# G431_Dev_V2.net
KiCad netlist of a schematic drawn in Altium Designer
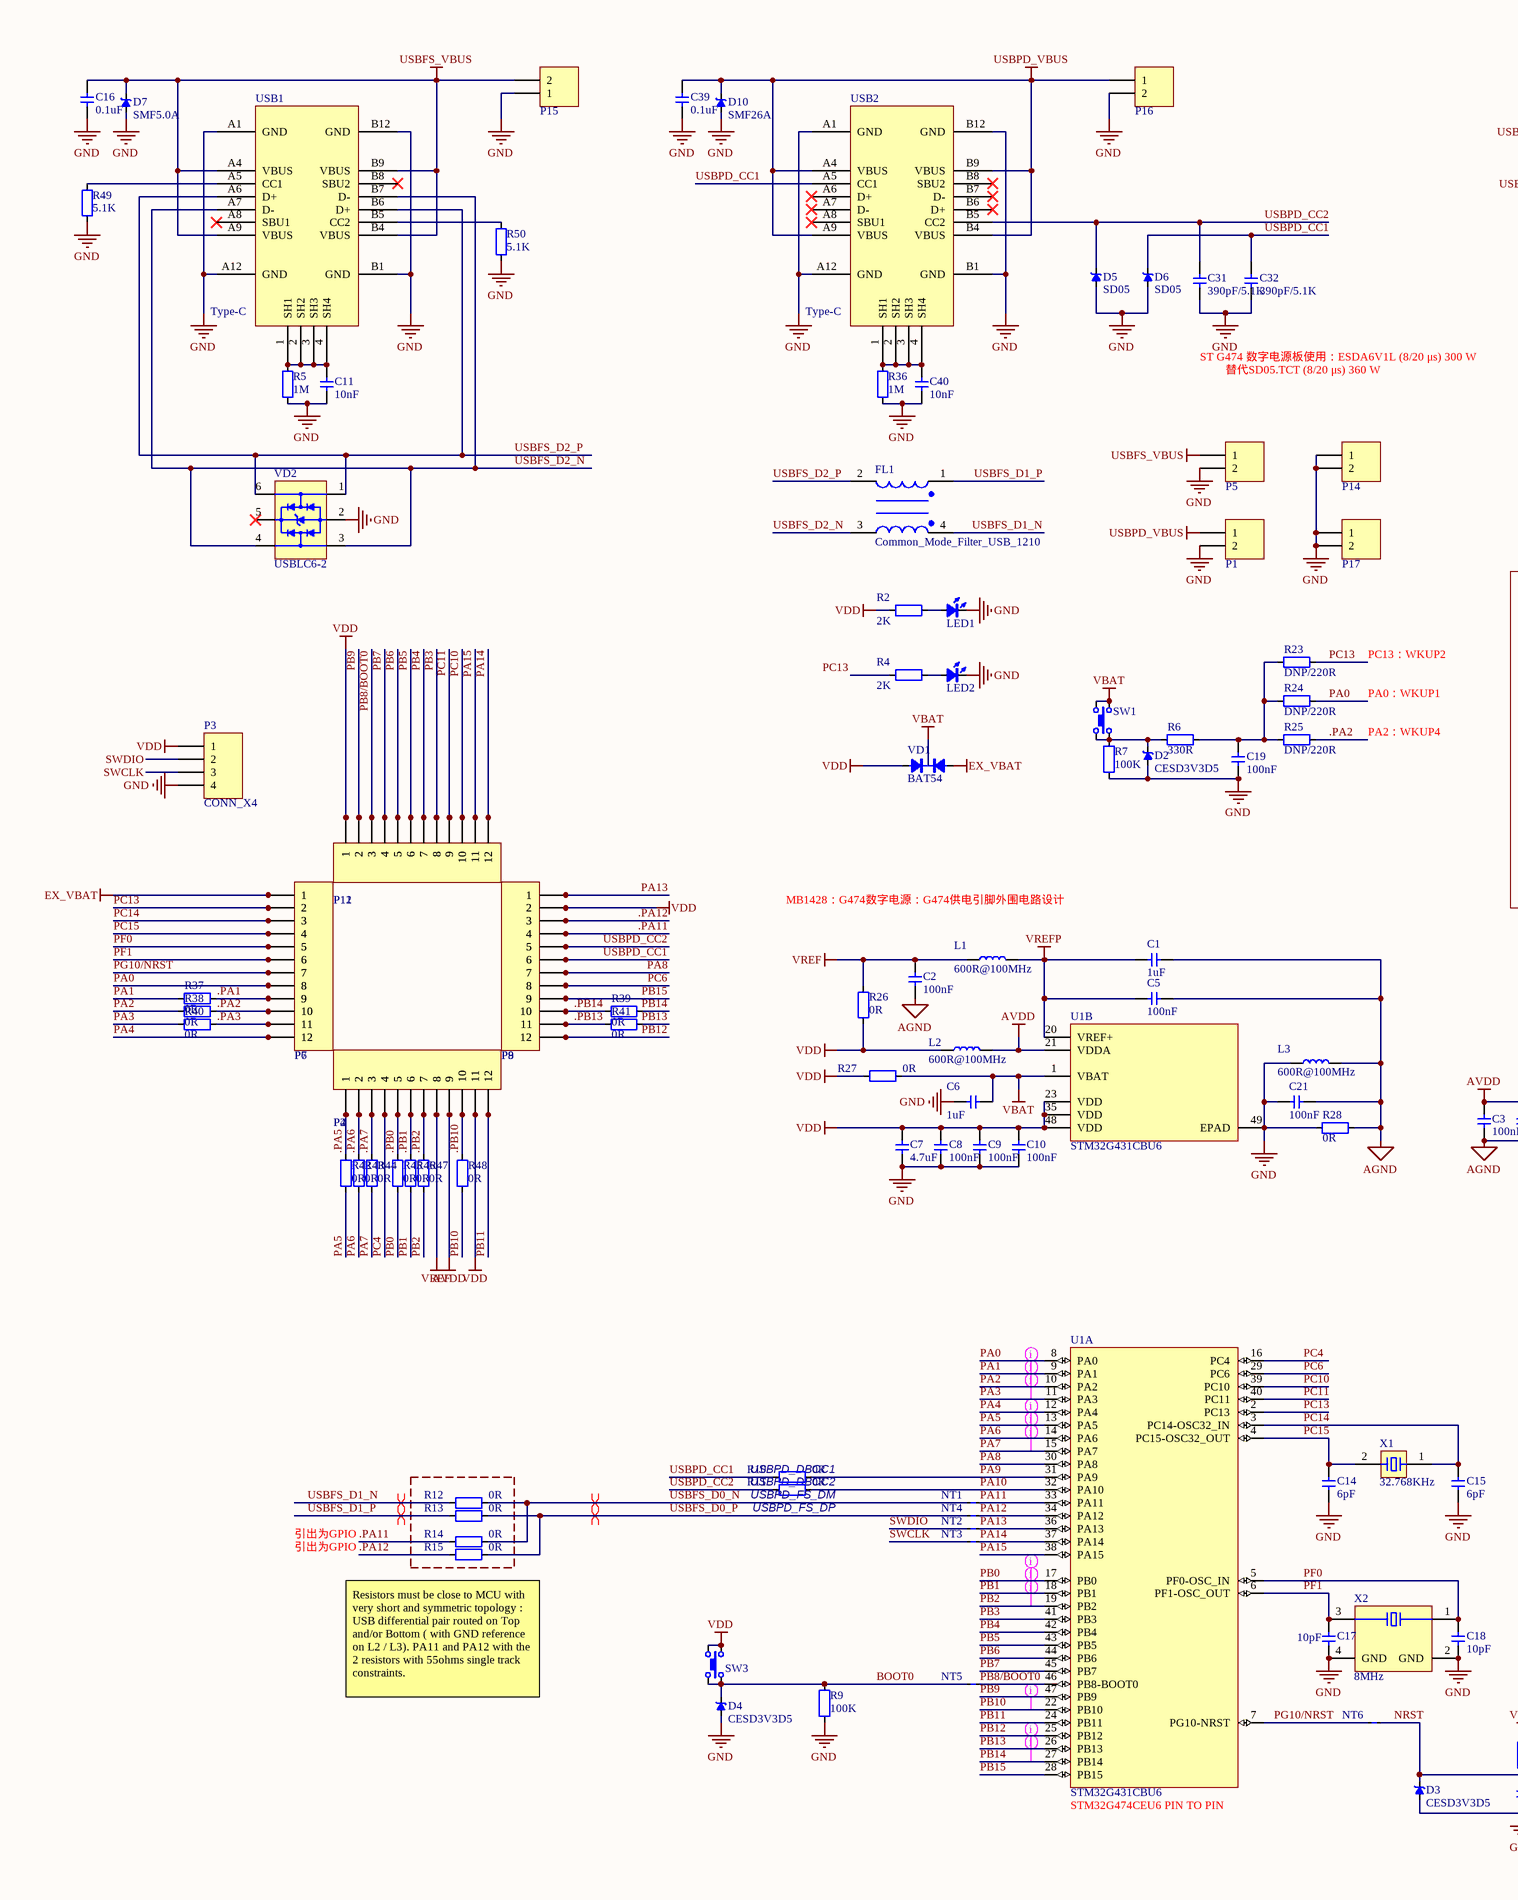
[diagram p0: G431_Dev_V2.SchDoc, left]
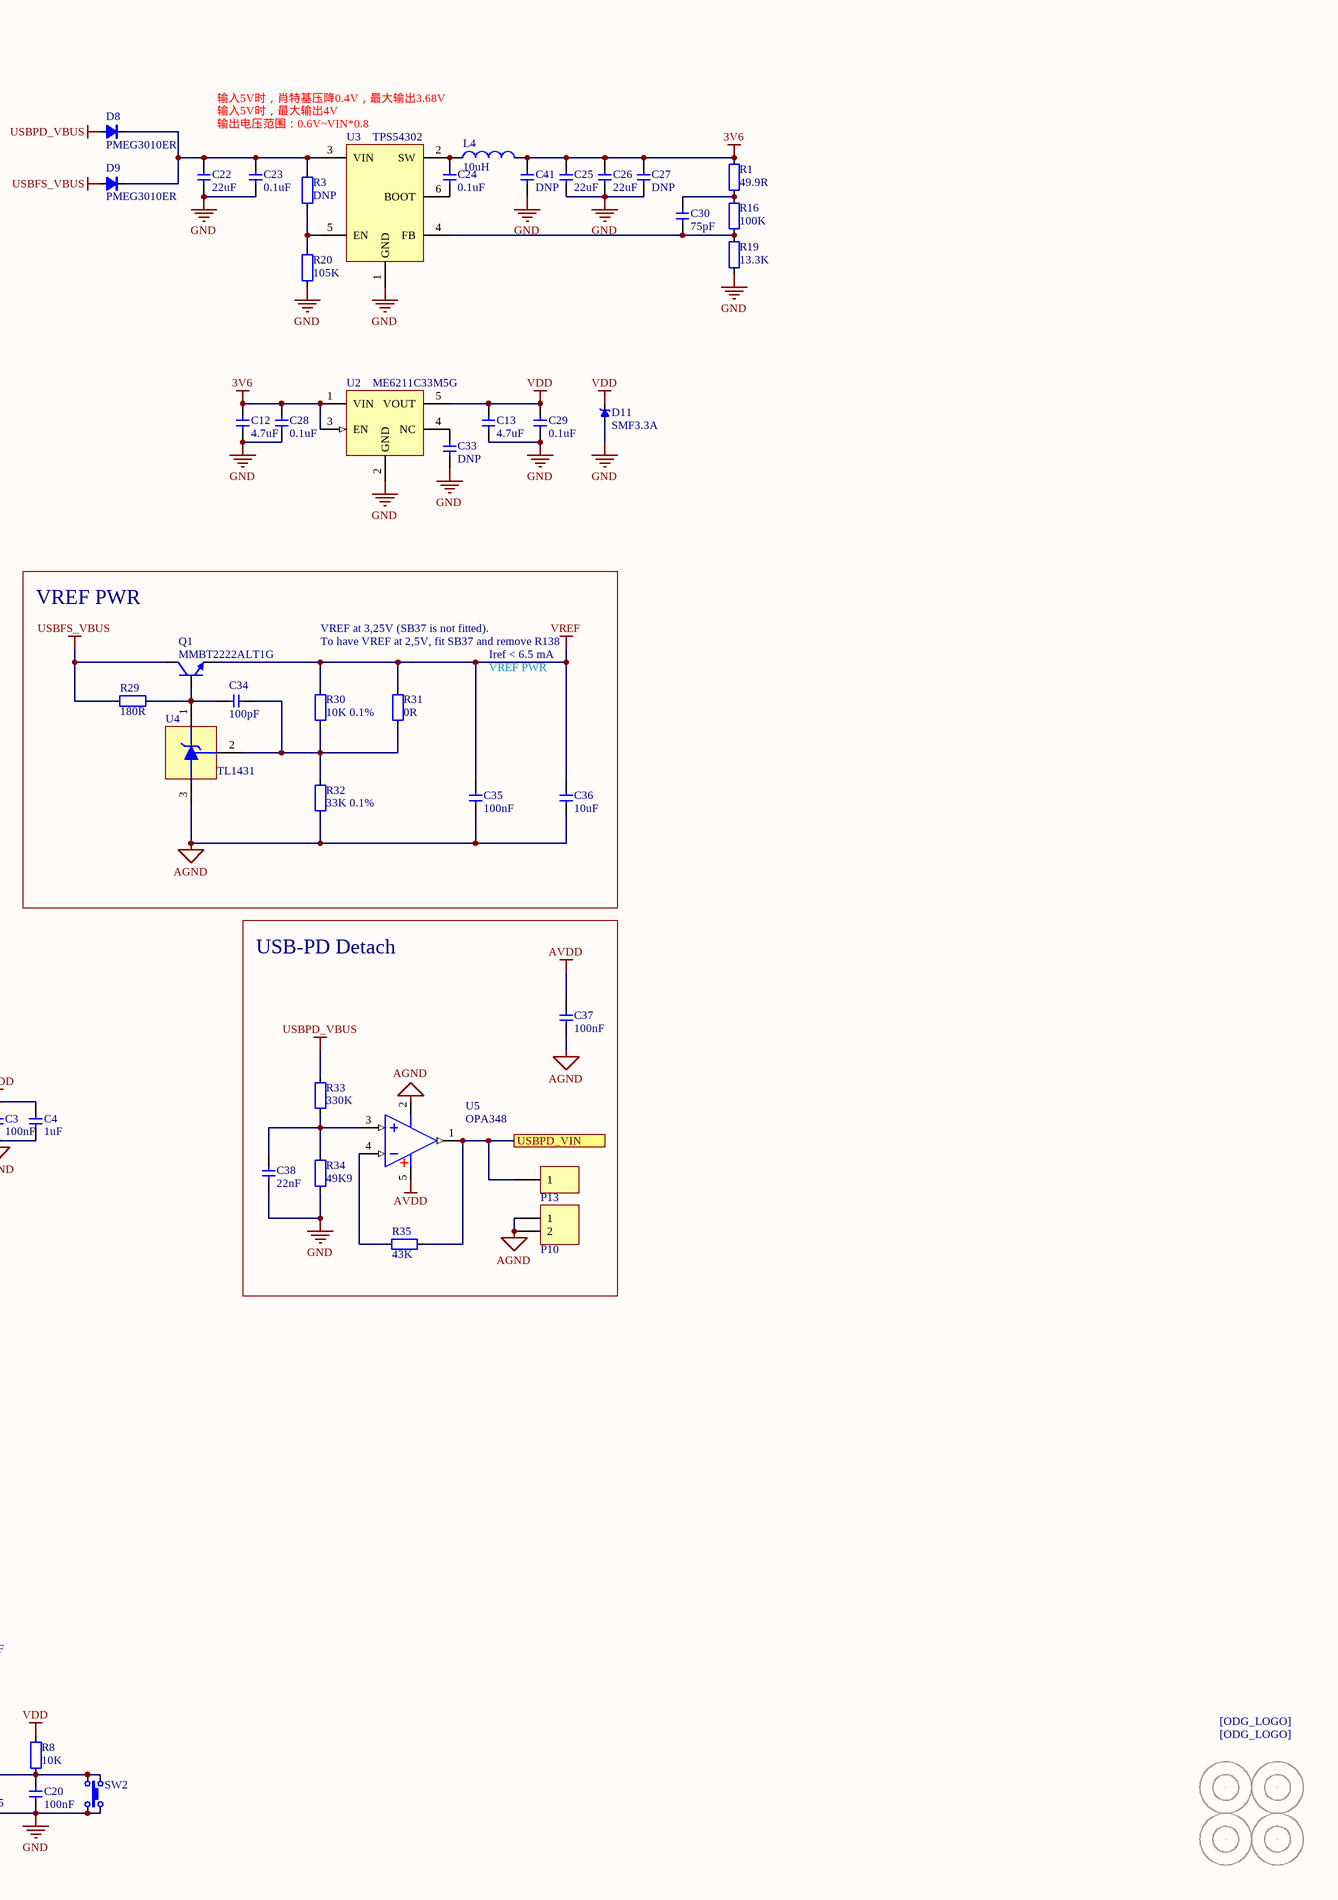
[diagram p1: G431_Dev_V2.SchDoc, right]

(export (version "E")
  (design (tool "Eeschema 10.0.6"))
  (components
    (comp (ref "*1")
      (value "ODG_LOGO")
      (footprint "ODG_LOGO")
      (libsource (lib "ODG_AD_Lib") (part "ODG_LOGO"))
    )
    (comp (ref "*2")
      (value "ODG_LOGO")
      (footprint "ODG_LOGO")
      (libsource (lib "ODG_AD_Lib") (part "ODG_LOGO"))
    )
    (comp (ref "C1")
      (value "1uF")
      (footprint "C0603")
      (description "Capacitor")
      (libsource (lib "ODG_AD_Lib") (part "CAP"))
    )
    (comp (ref "C2")
      (value "100nF")
      (footprint "C0402")
      (description "Capacitor")
      (libsource (lib "ODG_AD_Lib") (part "CAP"))
    )
    (comp (ref "C3")
      (value "100nF")
      (footprint "C0402")
      (description "Capacitor")
      (libsource (lib "ODG_AD_Lib") (part "CAP"))
    )
    (comp (ref "C4")
      (value "1uF")
      (footprint "C0603")
      (description "Capacitor")
      (libsource (lib "ODG_AD_Lib") (part "CAP"))
    )
    (comp (ref "C5")
      (value "100nF")
      (footprint "C0402")
      (description "Capacitor")
      (libsource (lib "ODG_AD_Lib") (part "CAP"))
    )
    (comp (ref "C6")
      (value "1uF")
      (footprint "C0603")
      (description "Capacitor")
      (libsource (lib "ODG_AD_Lib") (part "CAP"))
    )
    (comp (ref "C7")
      (value "4.7uF")
      (footprint "C0603")
      (description "Capacitor")
      (libsource (lib "ODG_AD_Lib") (part "CAP"))
    )
    (comp (ref "C8")
      (value "100nF")
      (footprint "C0402")
      (description "Capacitor")
      (libsource (lib "ODG_AD_Lib") (part "CAP"))
    )
    (comp (ref "C9")
      (value "100nF")
      (footprint "C0402")
      (description "Capacitor")
      (libsource (lib "ODG_AD_Lib") (part "CAP"))
    )
    (comp (ref "C10")
      (value "100nF")
      (footprint "C0402")
      (description "Capacitor")
      (libsource (lib "ODG_AD_Lib") (part "CAP"))
    )
    (comp (ref "C11")
      (value "10nF")
      (footprint "C0402")
      (description "Capacitor")
      (libsource (lib "ODG_AD_Lib") (part "CAP"))
    )
    (comp (ref "C12")
      (value "4.7uF")
      (footprint "C0603")
      (description "Capacitor")
      (libsource (lib "ODG_AD_Lib") (part "CAP"))
    )
    (comp (ref "C13")
      (value "4.7uF")
      (footprint "C0603")
      (description "Capacitor")
      (libsource (lib "ODG_AD_Lib") (part "CAP"))
    )
    (comp (ref "C14")
      (value "6pF")
      (footprint "C0402")
      (description "Capacitor")
      (libsource (lib "ODG_AD_Lib") (part "CAP"))
    )
    (comp (ref "C15")
      (value "6pF")
      (footprint "C0402")
      (description "Capacitor")
      (libsource (lib "ODG_AD_Lib") (part "CAP"))
    )
    (comp (ref "C16")
      (value "0.1uF")
      (footprint "C0402")
      (description "Capacitor")
      (libsource (lib "ODG_AD_Lib") (part "CAP"))
    )
    (comp (ref "C17")
      (value "10pF")
      (footprint "C0402")
      (description "Capacitor")
      (libsource (lib "ODG_AD_Lib") (part "CAP"))
    )
    (comp (ref "C18")
      (value "10pF")
      (footprint "C0402")
      (description "Capacitor")
      (libsource (lib "ODG_AD_Lib") (part "CAP"))
    )
    (comp (ref "C19")
      (value "100nF")
      (footprint "C0402")
      (description "Capacitor")
      (libsource (lib "ODG_AD_Lib") (part "CAP"))
    )
    (comp (ref "C20")
      (value "100nF")
      (footprint "C0402")
      (description "Capacitor")
      (libsource (lib "ODG_AD_Lib") (part "CAP"))
    )
    (comp (ref "C21")
      (value "100nF")
      (footprint "C0402")
      (description "Capacitor")
      (libsource (lib "ODG_AD_Lib") (part "CAP"))
    )
    (comp (ref "C22")
      (value "22uF")
      (footprint "C1206")
      (description "Capacitor")
      (libsource (lib "ODG_AD_Lib") (part "CAP"))
    )
    (comp (ref "C23")
      (value "0.1uF")
      (footprint "C0402")
      (description "Capacitor")
      (libsource (lib "ODG_AD_Lib") (part "CAP"))
    )
    (comp (ref "C24")
      (value "0.1uF")
      (footprint "C0402")
      (description "Capacitor")
      (libsource (lib "ODG_AD_Lib") (part "CAP"))
    )
    (comp (ref "C25")
      (value "22uF")
      (footprint "C0805")
      (description "Capacitor")
      (libsource (lib "ODG_AD_Lib") (part "CAP"))
    )
    (comp (ref "C26")
      (value "22uF")
      (footprint "C0805")
      (description "Capacitor")
      (libsource (lib "ODG_AD_Lib") (part "CAP"))
    )
    (comp (ref "C27")
      (value "DNP")
      (footprint "C0603")
      (description "Capacitor")
      (libsource (lib "ODG_AD_Lib") (part "CAP"))
    )
    (comp (ref "C28")
      (value "0.1uF")
      (footprint "C0402")
      (description "Capacitor")
      (libsource (lib "ODG_AD_Lib") (part "CAP"))
    )
    (comp (ref "C29")
      (value "0.1uF")
      (footprint "C0402")
      (description "Capacitor")
      (libsource (lib "ODG_AD_Lib") (part "CAP"))
    )
    (comp (ref "C30")
      (value "75pF")
      (footprint "C0402")
      (description "Capacitor")
      (libsource (lib "ODG_AD_Lib") (part "CAP"))
    )
    (comp (ref "C31")
      (value "390pF/5.1K")
      (footprint "C0402")
      (description "Capacitor")
      (libsource (lib "ODG_AD_Lib") (part "CAP"))
    )
    (comp (ref "C32")
      (value "390pF/5.1K")
      (footprint "C0402")
      (description "Capacitor")
      (libsource (lib "ODG_AD_Lib") (part "CAP"))
    )
    (comp (ref "C33")
      (value "DNP")
      (footprint "C0402")
      (description "Capacitor")
      (libsource (lib "ODG_AD_Lib") (part "CAP"))
    )
    (comp (ref "C34")
      (value "100pF")
      (footprint "C0402")
      (description "Capacitor")
      (libsource (lib "ODG_AD_Lib") (part "CAP"))
    )
    (comp (ref "C35")
      (value "100nF")
      (footprint "C0402")
      (description "Capacitor")
      (libsource (lib "ODG_AD_Lib") (part "CAP"))
    )
    (comp (ref "C36")
      (value "10uF")
      (footprint "C0603")
      (description "Capacitor")
      (libsource (lib "ODG_AD_Lib") (part "CAP"))
    )
    (comp (ref "C37")
      (value "100nF")
      (footprint "C0402")
      (description "Capacitor")
      (libsource (lib "ODG_AD_Lib") (part "CAP"))
    )
    (comp (ref "C38")
      (value "22nF")
      (footprint "C0402")
      (description "Capacitor")
      (libsource (lib "ODG_AD_Lib") (part "CAP"))
    )
    (comp (ref "C39")
      (value "0.1uF")
      (footprint "C0402")
      (description "Capacitor")
      (libsource (lib "ODG_AD_Lib") (part "CAP"))
    )
    (comp (ref "C40")
      (value "10nF")
      (footprint "C0402")
      (description "Capacitor")
      (libsource (lib "ODG_AD_Lib") (part "CAP"))
    )
    (comp (ref "C41")
      (value "DNP")
      (footprint "C0805")
      (description "Capacitor")
      (libsource (lib "ODG_AD_Lib") (part "CAP"))
    )
    (comp (ref "D2")
      (value "CESD3V3D5")
      (footprint "SOD-523")
      (description "极性：Unidirectional")
      (fields
        (field (name "MF") "Taiwan Semiconductor Corporation")
        (field (name "DIGI-KEY_PART_NUMBER") "TESD5V0L1UCRJGTR-ND")
      )
      (libsource (lib "ODG_AD_Lib") (part "TVS_U"))
    )
    (comp (ref "D3")
      (value "CESD3V3D5")
      (footprint "SOD-523")
      (description "极性：Unidirectional")
      (fields
        (field (name "MF") "Taiwan Semiconductor Corporation")
        (field (name "DIGI-KEY_PART_NUMBER") "TESD5V0L1UCRJGTR-ND")
      )
      (libsource (lib "ODG_AD_Lib") (part "TVS_U"))
    )
    (comp (ref "D4")
      (value "CESD3V3D5")
      (footprint "SOD-523")
      (description "极性：Unidirectional")
      (fields
        (field (name "MF") "Taiwan Semiconductor Corporation")
        (field (name "DIGI-KEY_PART_NUMBER") "TESD5V0L1UCRJGTR-ND")
      )
      (libsource (lib "ODG_AD_Lib") (part "TVS_U"))
    )
    (comp (ref "D5")
      (value "SD05")
      (footprint "SOD-323")
      (description "极性：Unidirectional")
      (fields
        (field (name "MF") "Taiwan Semiconductor Corporation")
        (field (name "DIGI-KEY_PART_NUMBER") "TESD5V0L1UCRJGTR-ND")
      )
      (libsource (lib "ODG_AD_Lib") (part "TVS_U"))
    )
    (comp (ref "D6")
      (value "SD05")
      (footprint "SOD-323")
      (description "极性：Unidirectional")
      (fields
        (field (name "MF") "Taiwan Semiconductor Corporation")
        (field (name "DIGI-KEY_PART_NUMBER") "TESD5V0L1UCRJGTR-ND")
      )
      (libsource (lib "ODG_AD_Lib") (part "TVS_U"))
    )
    (comp (ref "D7")
      (value "SMF5.0A")
      (footprint "SOD123F")
      (description "极性：Unidirectional")
      (fields
        (field (name "MF") "Taiwan Semiconductor Corporation")
        (field (name "DIGI-KEY_PART_NUMBER") "TESD5V0L1UCRJGTR-ND")
      )
      (libsource (lib "ODG_AD_Lib") (part "TVS_U"))
    )
    (comp (ref "D8")
      (value "PMEG3010ER")
      (footprint "SOD123F")
      (description "二极管")
      (libsource (lib "ODG_AD_Lib") (part "DIODE"))
    )
    (comp (ref "D9")
      (value "PMEG3010ER")
      (footprint "SOD123F")
      (description "二极管")
      (libsource (lib "ODG_AD_Lib") (part "DIODE"))
    )
    (comp (ref "D10")
      (value "SMF26A")
      (footprint "SOD123F")
      (description "极性：Unidirectional")
      (fields
        (field (name "MF") "Taiwan Semiconductor Corporation")
        (field (name "DIGI-KEY_PART_NUMBER") "TESD5V0L1UCRJGTR-ND")
      )
      (libsource (lib "ODG_AD_Lib") (part "TVS_U"))
    )
    (comp (ref "D11")
      (value "SMF3.3A")
      (footprint "SOD123F")
      (description "极性：Unidirectional")
      (fields
        (field (name "MF") "Taiwan Semiconductor Corporation")
        (field (name "DIGI-KEY_PART_NUMBER") "TESD5V0L1UCRJGTR-ND")
      )
      (libsource (lib "ODG_AD_Lib") (part "TVS_U"))
    )
    (comp (ref "FL1")
      (value "Common_Mode_Filter_USB_1210")
      (footprint "FIL_1210_DLP11RB400UL2L")
      (description "Chip Common Mode Choke Coil")
      (fields (field (name "MP") "DLP11RB400UL2L"))
      (libsource (lib "ODG_AD_Lib") (part "Common_Mode_Filter_USB"))
    )
    (comp (ref "H1") (value "HOLE") (footprint "M2.1 D=4.2") (libsource (lib "ODG_AD_Lib") (part "HOLE")))
    (comp (ref "H2") (value "HOLE") (footprint "M2.1 D=4.2") (libsource (lib "ODG_AD_Lib") (part "HOLE")))
    (comp (ref "H3") (value "HOLE") (footprint "M2.1 D=4.2") (libsource (lib "ODG_AD_Lib") (part "HOLE")))
    (comp (ref "H4") (value "HOLE") (footprint "M2.1 D=4.2") (libsource (lib "ODG_AD_Lib") (part "HOLE")))
    (comp (ref "L1")
      (value "600R@100MHz")
      (footprint "FER0603")
      (description "贴片叠层电感")
      (libsource (lib "ODG_AD_Lib") (part "inductor_mini"))
    )
    (comp (ref "L2")
      (value "600R@100MHz")
      (footprint "FER0603")
      (description "贴片叠层电感")
      (libsource (lib "ODG_AD_Lib") (part "inductor_mini"))
    )
    (comp (ref "L3")
      (value "600R@100MHz")
      (footprint "FER0603")
      (description "贴片叠层电感")
      (libsource (lib "ODG_AD_Lib") (part "inductor_mini"))
    )
    (comp (ref "L4")
      (value "10uH")
      (footprint "INDUCTOR 0420 4.6X4.1X2MM")
      (description "功率电感")
      (libsource (lib "ODG_AD_Lib") (part "Inductor_power"))
    )
    (comp (ref "LED1") (value "LED") (footprint "LED0603_GREEN") (libsource (lib "ODG_AD_Lib") (part "LED")))
    (comp (ref "LED2") (value "LED") (footprint "LED0603_BLUE") (libsource (lib "ODG_AD_Lib") (part "LED")))
    (comp (ref "NT1")
      (value "NetTie")
      (footprint "NetTie_D=10MIL_C=10MIL")
      (description "Net Tie")
      (fields (field (name "PART NUMBER") "NetTie 0.2mm") (field (name "PUBLISHER") "Nordic Semiconductor"))
      (libsource (lib "ODG_AD_Lib") (part "NetTie"))
    )
    (comp (ref "NT2")
      (value "NetTie")
      (footprint "NetTie_D=10MIL_C=10MIL")
      (description "Net Tie")
      (fields (field (name "PART NUMBER") "NetTie 0.2mm") (field (name "PUBLISHER") "Nordic Semiconductor"))
      (libsource (lib "ODG_AD_Lib") (part "NetTie"))
    )
    (comp (ref "NT3")
      (value "NetTie")
      (footprint "NetTie_D=10MIL_C=10MIL")
      (description "Net Tie")
      (fields (field (name "PART NUMBER") "NetTie 0.2mm") (field (name "PUBLISHER") "Nordic Semiconductor"))
      (libsource (lib "ODG_AD_Lib") (part "NetTie"))
    )
    (comp (ref "NT4")
      (value "NetTie")
      (footprint "NetTie_D=10MIL_C=10MIL")
      (description "Net Tie")
      (fields (field (name "PART NUMBER") "NetTie 0.2mm") (field (name "PUBLISHER") "Nordic Semiconductor"))
      (libsource (lib "ODG_AD_Lib") (part "NetTie"))
    )
    (comp (ref "NT5")
      (value "NetTie")
      (footprint "NetTie_D=10MIL_C=10MIL")
      (description "Net Tie")
      (fields (field (name "PART NUMBER") "NetTie 0.2mm") (field (name "PUBLISHER") "Nordic Semiconductor"))
      (libsource (lib "ODG_AD_Lib") (part "NetTie"))
    )
    (comp (ref "NT6")
      (value "NetTie")
      (footprint "NetTie_D=10MIL_C=10MIL")
      (description "Net Tie")
      (fields (field (name "PART NUMBER") "NetTie 0.2mm") (field (name "PUBLISHER") "Nordic Semiconductor"))
      (libsource (lib "ODG_AD_Lib") (part "NetTie"))
    )
    (comp (ref "P1")
      (value "CONN_X2")
      (footprint "2.54mm_Male_x2")
      (libsource (lib "ODG_AD_Lib") (part "CONN_X2"))
    )
    (comp (ref "P2")
      (value "CONN_X12")
      (footprint "2.54MM_MALE_X12")
      (libsource (lib "") (part "CONN_X12_3"))
    )
    (comp (ref "P3")
      (value "CONN_X4")
      (footprint "2.54mm_Male_x4")
      (libsource (lib "ODG_AD_Lib") (part "CONN_X4"))
    )
    (comp (ref "P4")
      (value "CONN_X12")
      (footprint "2.54MM_MALE_X12")
      (libsource (lib "") (part "CONN_X12_3"))
    )
    (comp (ref "P5")
      (value "CONN_X2")
      (footprint "2.54mm_Male_x2")
      (libsource (lib "ODG_AD_Lib") (part "CONN_X2"))
    )
    (comp (ref "P6")
      (value "CONN_X12")
      (footprint "2.54MM_MALE_X12")
      (libsource (lib "ODG_AD_Lib") (part "CONN_X12"))
    )
    (comp (ref "P7")
      (value "CONN_X12")
      (footprint "2.54MM_MALE_X12")
      (libsource (lib "ODG_AD_Lib") (part "CONN_X12"))
    )
    (comp (ref "P8")
      (value "CONN_X12")
      (footprint "2.54MM_MALE_X12")
      (libsource (lib "") (part "CONN_X12_1"))
    )
    (comp (ref "P9")
      (value "CONN_X12")
      (footprint "2.54MM_MALE_X12")
      (libsource (lib "") (part "CONN_X12_1"))
    )
    (comp (ref "P10")
      (value "CONN_X2")
      (footprint "2.54mm_Male_x2")
      (libsource (lib "ODG_AD_Lib") (part "CONN_X2"))
    )
    (comp (ref "P11")
      (value "CONN_X12")
      (footprint "2.54MM_MALE_X12")
      (libsource (lib "") (part "CONN_X12_2"))
    )
    (comp (ref "P12")
      (value "CONN_X12")
      (footprint "2.54MM_MALE_X12")
      (libsource (lib "") (part "CONN_X12_2"))
    )
    (comp (ref "P13")
      (value "CONN_X1")
      (footprint "2.54mm_Male_x1")
      (libsource (lib "ODG_AD_Lib") (part "CONN_X1"))
    )
    (comp (ref "P14")
      (value "CONN_X2")
      (footprint "2.54mm_Male_x2")
      (libsource (lib "ODG_AD_Lib") (part "CONN_X2"))
    )
    (comp (ref "P15") (value "CONN_X2") (footprint "TE_1776275-2") (libsource (lib "") (part "CONN_X2_1")))
    (comp (ref "P16")
      (value "CONN_X2")
      (footprint "TE_1776275-2")
      (libsource (lib "ODG_AD_Lib") (part "CONN_X2"))
    )
    (comp (ref "P17")
      (value "CONN_X2")
      (footprint "2.54mm_Male_x2")
      (libsource (lib "ODG_AD_Lib") (part "CONN_X2"))
    )
    (comp (ref "Q1")
      (value "MMBT2222ALT1G")
      (footprint "INFINEON SOT-23-3")
      (description "NPN型")
      (libsource (lib "ODG_AD_Lib") (part "NPN"))
    )
    (comp (ref "R1")
      (value "49.9R")
      (footprint "R0402")
      (description "IEC Standard")
      (libsource (lib "") (part "RES_2"))
    )
    (comp (ref "R2")
      (value "2K")
      (footprint "R0402")
      (description "IEC Standard")
      (libsource (lib "ODG_AD_Lib") (part "RES"))
    )
    (comp (ref "R3")
      (value "DNP")
      (footprint "R0402")
      (description "IEC Standard")
      (libsource (lib "") (part "RES_1"))
    )
    (comp (ref "R4")
      (value "2K")
      (footprint "R0402")
      (description "IEC Standard")
      (libsource (lib "ODG_AD_Lib") (part "RES"))
    )
    (comp (ref "R5")
      (value "1M")
      (footprint "R0402")
      (description "IEC Standard")
      (libsource (lib "") (part "RES_3"))
    )
    (comp (ref "R6")
      (value "330R")
      (footprint "R0402")
      (description "IEC Standard")
      (libsource (lib "") (part "RES_1"))
    )
    (comp (ref "R7")
      (value "100K")
      (footprint "R0402")
      (description "IEC Standard")
      (libsource (lib "") (part "RES_2"))
    )
    (comp (ref "R8")
      (value "10K")
      (footprint "R0402")
      (description "IEC Standard")
      (libsource (lib "") (part "RES_2"))
    )
    (comp (ref "R9")
      (value "100K")
      (footprint "R0402")
      (description "IEC Standard")
      (libsource (lib "") (part "RES_2"))
    )
    (comp (ref "R10")
      (value "0R")
      (footprint "R0402")
      (description "IEC Standard")
      (libsource (lib "ODG_AD_Lib") (part "RES"))
    )
    (comp (ref "R11")
      (value "0R")
      (footprint "R0402")
      (description "IEC Standard")
      (libsource (lib "ODG_AD_Lib") (part "RES"))
    )
    (comp (ref "R12")
      (value "0R")
      (footprint "R0402")
      (description "IEC Standard")
      (libsource (lib "ODG_AD_Lib") (part "RES"))
    )
    (comp (ref "R13")
      (value "0R")
      (footprint "R0402")
      (description "IEC Standard")
      (libsource (lib "ODG_AD_Lib") (part "RES"))
    )
    (comp (ref "R14")
      (value "0R")
      (footprint "R0402")
      (description "IEC Standard")
      (libsource (lib "ODG_AD_Lib") (part "RES"))
    )
    (comp (ref "R15")
      (value "0R")
      (footprint "R0402")
      (description "IEC Standard")
      (libsource (lib "ODG_AD_Lib") (part "RES"))
    )
    (comp (ref "R16")
      (value "100K")
      (footprint "R0402")
      (description "IEC Standard")
      (libsource (lib "") (part "RES_2"))
    )
    (comp (ref "R19")
      (value "13.3K")
      (footprint "R0402")
      (description "IEC Standard")
      (libsource (lib "") (part "RES_2"))
    )
    (comp (ref "R20")
      (value "105K")
      (footprint "R0402")
      (description "IEC Standard")
      (libsource (lib "") (part "RES_1"))
    )
    (comp (ref "R23")
      (value "DNP/220R")
      (footprint "R0402")
      (description "IEC Standard")
      (libsource (lib "") (part "RES_1"))
    )
    (comp (ref "R24")
      (value "DNP/220R")
      (footprint "R0402")
      (description "IEC Standard")
      (libsource (lib "") (part "RES_1"))
    )
    (comp (ref "R25")
      (value "DNP/220R")
      (footprint "R0402")
      (description "IEC Standard")
      (libsource (lib "") (part "RES_1"))
    )
    (comp (ref "R26")
      (value "0R")
      (footprint "R0402")
      (description "IEC Standard")
      (libsource (lib "") (part "RES_3"))
    )
    (comp (ref "R27")
      (value "0R")
      (footprint "R0402")
      (description "IEC Standard")
      (libsource (lib "ODG_AD_Lib") (part "RES"))
    )
    (comp (ref "R28")
      (value "0R")
      (footprint "R0402")
      (description "IEC Standard")
      (libsource (lib "") (part "RES_1"))
    )
    (comp (ref "R29")
      (value "180R")
      (footprint "R0402")
      (description "IEC Standard")
      (libsource (lib "") (part "RES_1"))
    )
    (comp (ref "R30")
      (value "10K 0.1%")
      (footprint "R0402")
      (description "IEC Standard")
      (libsource (lib "") (part "RES_3"))
    )
    (comp (ref "R31")
      (value "0R")
      (footprint "R0402")
      (description "IEC Standard")
      (libsource (lib "") (part "RES_3"))
    )
    (comp (ref "R32")
      (value "33K 0.1%")
      (footprint "R0402")
      (description "IEC Standard")
      (libsource (lib "") (part "RES_3"))
    )
    (comp (ref "R33")
      (value "330K")
      (footprint "R0402")
      (description "IEC Standard")
      (libsource (lib "") (part "RES_3"))
    )
    (comp (ref "R34")
      (value "49K9")
      (footprint "R0402")
      (description "IEC Standard")
      (libsource (lib "") (part "RES_2"))
    )
    (comp (ref "R35")
      (value "43K")
      (footprint "R0402")
      (description "IEC Standard")
      (libsource (lib "") (part "RES_1"))
    )
    (comp (ref "R36")
      (value "1M")
      (footprint "R0402")
      (description "IEC Standard")
      (libsource (lib "") (part "RES_3"))
    )
    (comp (ref "R37")
      (value "0R")
      (footprint "RES_TINY_0402")
      (description "IEC Standard")
      (libsource (lib "ODG_AD_Lib") (part "RES"))
    )
    (comp (ref "R38")
      (value "0R")
      (footprint "RES_TINY_0402")
      (description "IEC Standard")
      (libsource (lib "ODG_AD_Lib") (part "RES"))
    )
    (comp (ref "R39")
      (value "0R")
      (footprint "RES_TINY_0402")
      (description "IEC Standard")
      (libsource (lib "ODG_AD_Lib") (part "RES"))
    )
    (comp (ref "R40")
      (value "0R")
      (footprint "RES_TINY_0402")
      (description "IEC Standard")
      (libsource (lib "ODG_AD_Lib") (part "RES"))
    )
    (comp (ref "R41")
      (value "0R")
      (footprint "RES_TINY_0402")
      (description "IEC Standard")
      (libsource (lib "ODG_AD_Lib") (part "RES"))
    )
    (comp (ref "R42")
      (value "0R")
      (footprint "RES_TINY_0402")
      (description "IEC Standard")
      (libsource (lib "") (part "RES_2"))
    )
    (comp (ref "R43")
      (value "0R")
      (footprint "RES_TINY_0402")
      (description "IEC Standard")
      (libsource (lib "") (part "RES_2"))
    )
    (comp (ref "R44")
      (value "0R")
      (footprint "RES_TINY_0402")
      (description "IEC Standard")
      (libsource (lib "") (part "RES_2"))
    )
    (comp (ref "R45")
      (value "0R")
      (footprint "RES_TINY_0402")
      (description "IEC Standard")
      (libsource (lib "") (part "RES_2"))
    )
    (comp (ref "R46")
      (value "0R")
      (footprint "RES_TINY_0402")
      (description "IEC Standard")
      (libsource (lib "") (part "RES_2"))
    )
    (comp (ref "R47")
      (value "0R")
      (footprint "RES_TINY_0402")
      (description "IEC Standard")
      (libsource (lib "") (part "RES_2"))
    )
    (comp (ref "R48")
      (value "0R")
      (footprint "RES_TINY_0402")
      (description "IEC Standard")
      (libsource (lib "") (part "RES_2"))
    )
    (comp (ref "R49")
      (value "5.1K")
      (footprint "R0402")
      (description "IEC Standard")
      (libsource (lib "") (part "RES_3"))
    )
    (comp (ref "R50")
      (value "5.1K")
      (footprint "R0402")
      (description "IEC Standard")
      (libsource (lib "") (part "RES_2"))
    )
    (comp (ref "SW1")
      (value "Button-4P")
      (footprint "SWITCH_3X4X2.5_4PIN_SMD")
      (description "Button")
      (libsource (lib "ODG_AD_Lib") (part "Button-4P"))
    )
    (comp (ref "SW2")
      (value "Button-4P")
      (footprint "SWITCH_3X4X2.5_4PIN_SMD")
      (description "Button")
      (libsource (lib "ODG_AD_Lib") (part "Button-4P"))
    )
    (comp (ref "SW3")
      (value "Button-4P")
      (footprint "SWITCH_3X4X2.5_4PIN_SMD")
      (description "Button")
      (libsource (lib "ODG_AD_Lib") (part "Button-4P"))
    )
    (comp (ref "U1")
      (value "STM32G431CBU6")
      (footprint "UFQFPN-48_7X7X0P55MM")
      (fields (field (name "COPYRIGHT") "Copyright (C) 2023 Ultra Librarian. All rights reserved."))
      (libsource (lib "ODG_Project") (part "STM32G431CBU6"))
    )
    (comp (ref "U2")
      (value "ME6211C33M5G")
      (footprint "ANALOG TSOT-23-5 UJ-5")
      (description "线性稳压芯片")
      (libsource (lib "ODG_AD_Lib") (part "ME6211C33M5G"))
    )
    (comp (ref "U3")
      (value "TPS54302")
      (footprint "MICROCHIP SOT-23-6 M6")
      (description "4.5-V to 28-V Input, 3-A Output, EMI Friendly Synchronous Step Down Converter")
      (libsource (lib "ODG_Project") (part "TPS54302"))
    )
    (comp (ref "U4")
      (value "TL1431")
      (footprint "INFINEON SOT-23-3")
      (description "Programmable voltage reference")
      (libsource (lib "ODG_AD_Lib") (part "TL1431 (SOT23-3)"))
    )
    (comp (ref "U5")
      (value "OPA348")
      (footprint "ANALOG SOT-23-5 RJ-5")
      (description "精密、低噪声、CMOS、轨到轨输入/输出运算放大器")
      (libsource (lib "ODG_AD_Lib") (part "AD8605ARTZ"))
    )
    (comp (ref "USB1")
      (value "Type-C")
      (footprint "Type-C-TOP")
      (libsource (lib "ODG_AD_Lib") (part "USB-Type-C_16P"))
    )
    (comp (ref "USB2")
      (value "Type-C")
      (footprint "Type-C-TOP")
      (libsource (lib "ODG_AD_Lib") (part "USB-Type-C_16P"))
    )
    (comp (ref "VD1")
      (value "BAT54")
      (footprint "INFINEON SOT-23-3")
      (description "贴片肖特基二极管")
      (libsource (lib "ODG_AD_Lib") (part "BAT54C"))
    )
    (comp (ref "VD2")
      (value "USBLC6-2")
      (footprint "MICROCHIP SOT-23-6 M6")
      (libsource (lib "ODG_AD_Lib") (part "USBLC6-2"))
    )
    (comp (ref "X1")
      (value "32.768KHz")
      (footprint "XTAL_2P_3215")
      (description "2脚无源石英晶振")
      (fields (field (name "版权归属") "源创客"))
      (libsource (lib "ODG_AD_Lib") (part "XTAL-2P"))
    )
    (comp (ref "X2")
      (value "8MHz")
      (footprint "EPSON TSX-3225")
      (description "4脚无源石英晶振")
      (fields (field (name "版权归属") "源创客"))
      (libsource (lib "ODG_AD_Lib") (part "XTAL-4P"))
    )
  )
  (nets
    (net (code "1") (name "/.PA1") (class "Default")
      (node (ref "P6") (pin "9") (pinfunction "9_9") (pintype "passive"))
      (node (ref "P7") (pin "9") (pinfunction "9_9") (pintype "passive"))
      (node (ref "R37") (pin "2") (pinfunction "2_2") (pintype "passive"))
    )
    (net (code "2") (name "/.PA2") (class "Default")
      (node (ref "P6") (pin "10") (pinfunction "10_10") (pintype "passive"))
      (node (ref "P7") (pin "10") (pinfunction "10_10") (pintype "passive"))
      (node (ref "R25") (pin "1") (pinfunction "1_1") (pintype "passive"))
      (node (ref "R38") (pin "2") (pinfunction "2_2") (pintype "passive"))
    )
    (net (code "3") (name "/.PA3") (class "Default")
      (node (ref "P6") (pin "11") (pinfunction "11_11") (pintype "passive"))
      (node (ref "P7") (pin "11") (pinfunction "11_11") (pintype "passive"))
      (node (ref "R40") (pin "2") (pinfunction "2_2") (pintype "passive"))
    )
    (net (code "4") (name "/.PA5") (class "Default")
      (node (ref "P2") (pin "1") (pinfunction "1_1") (pintype "passive"))
      (node (ref "P4") (pin "1") (pinfunction "1_1") (pintype "passive"))
      (node (ref "R42") (pin "1") (pinfunction "1_1") (pintype "passive"))
    )
    (net (code "5") (name "/.PA6") (class "Default")
      (node (ref "P2") (pin "2") (pinfunction "2_2") (pintype "passive"))
      (node (ref "P4") (pin "2") (pinfunction "2_2") (pintype "passive"))
      (node (ref "R43") (pin "1") (pinfunction "1_1") (pintype "passive"))
    )
    (net (code "6") (name "/.PA7") (class "Default")
      (node (ref "P2") (pin "3") (pinfunction "3_3") (pintype "passive"))
      (node (ref "P4") (pin "3") (pinfunction "3_3") (pintype "passive"))
      (node (ref "R44") (pin "1") (pinfunction "1_1") (pintype "passive"))
    )
    (net (code "7") (name "/.PA11") (class "Default")
      (node (ref "P8") (pin "4") (pinfunction "4_4") (pintype "passive"))
      (node (ref "P9") (pin "4") (pinfunction "4_4") (pintype "passive"))
      (node (ref "R14") (pin "1") (pinfunction "1_1") (pintype "passive"))
    )
    (net (code "8") (name "/.PA12") (class "Default")
      (node (ref "P8") (pin "3") (pinfunction "3_3") (pintype "passive"))
      (node (ref "P9") (pin "3") (pinfunction "3_3") (pintype "passive"))
      (node (ref "R15") (pin "1") (pinfunction "1_1") (pintype "passive"))
    )
    (net (code "9") (name "/.PB0") (class "Default")
      (node (ref "P2") (pin "5") (pinfunction "5_5") (pintype "passive"))
      (node (ref "P4") (pin "5") (pinfunction "5_5") (pintype "passive"))
      (node (ref "R45") (pin "1") (pinfunction "1_1") (pintype "passive"))
    )
    (net (code "10") (name "/.PB1") (class "Default")
      (node (ref "P2") (pin "6") (pinfunction "6_6") (pintype "passive"))
      (node (ref "P4") (pin "6") (pinfunction "6_6") (pintype "passive"))
      (node (ref "R46") (pin "1") (pinfunction "1_1") (pintype "passive"))
    )
    (net (code "11") (name "/.PB2") (class "Default")
      (node (ref "P2") (pin "7") (pinfunction "7_7") (pintype "passive"))
      (node (ref "P4") (pin "7") (pinfunction "7_7") (pintype "passive"))
      (node (ref "R47") (pin "1") (pinfunction "1_1") (pintype "passive"))
    )
    (net (code "12") (name "/.PB10") (class "Default")
      (node (ref "P2") (pin "10") (pinfunction "10_10") (pintype "passive"))
      (node (ref "P4") (pin "10") (pinfunction "10_10") (pintype "passive"))
      (node (ref "R48") (pin "1") (pinfunction "1_1") (pintype "passive"))
    )
    (net (code "13") (name "/.PB13") (class "Default")
      (node (ref "P8") (pin "11") (pinfunction "11_11") (pintype "passive"))
      (node (ref "P9") (pin "11") (pinfunction "11_11") (pintype "passive"))
      (node (ref "R41") (pin "1") (pinfunction "1_1") (pintype "passive"))
    )
    (net (code "14") (name "/.PB14") (class "Default")
      (node (ref "P8") (pin "10") (pinfunction "10_10") (pintype "passive"))
      (node (ref "P9") (pin "10") (pinfunction "10_10") (pintype "passive"))
      (node (ref "R39") (pin "1") (pinfunction "1_1") (pintype "passive"))
    )
    (net (code "15") (name "/BOOT0") (class "Default")
      (node (ref "D4") (pin "2") (pinfunction "2_2") (pintype "passive"))
      (node (ref "NT5") (pin "2") (pinfunction "2_2") (pintype "passive"))
      (node (ref "R9") (pin "1") (pinfunction "1_1") (pintype "passive"))
      (node (ref "SW3") (pin "1") (pinfunction "1_1") (pintype "passive"))
      (node (ref "SW3") (pin "2") (pinfunction "2_2") (pintype "passive"))
    )
    (net (code "16") (name "/NRST") (class "Default")
      (node (ref "C20") (pin "2") (pinfunction "2_2") (pintype "passive"))
      (node (ref "D3") (pin "2") (pinfunction "2_2") (pintype "passive"))
      (node (ref "NT6") (pin "1") (pinfunction "1_1") (pintype "passive"))
      (node (ref "R8") (pin "2") (pinfunction "2_2") (pintype "passive"))
      (node (ref "SW2") (pin "1") (pinfunction "1_1") (pintype "passive"))
      (node (ref "SW2") (pin "2") (pinfunction "2_2") (pintype "passive"))
    )
    (net (code "17") (name "/PA0") (class "Default")
      (node (ref "P6") (pin "8") (pinfunction "8_8") (pintype "passive"))
      (node (ref "P7") (pin "8") (pinfunction "8_8") (pintype "passive"))
      (node (ref "R24") (pin "1") (pinfunction "1_1") (pintype "passive"))
      (node (ref "U1") (pin "8") (pinfunction "PA0_8") (pintype "bidirectional"))
    )
    (net (code "18") (name "/PA1") (class "Default")
      (node (ref "R37") (pin "1") (pinfunction "1_1") (pintype "passive"))
      (node (ref "U1") (pin "9") (pinfunction "PA1_9") (pintype "bidirectional"))
    )
    (net (code "19") (name "/PA2") (class "Default")
      (node (ref "R38") (pin "1") (pinfunction "1_1") (pintype "passive"))
      (node (ref "U1") (pin "10") (pinfunction "PA2_10") (pintype "bidirectional"))
    )
    (net (code "20") (name "/PA3") (class "Default")
      (node (ref "R40") (pin "1") (pinfunction "1_1") (pintype "passive"))
      (node (ref "U1") (pin "11") (pinfunction "PA3_11") (pintype "bidirectional"))
    )
    (net (code "21") (name "/PA4") (class "Default")
      (node (ref "P6") (pin "12") (pinfunction "12_12") (pintype "passive"))
      (node (ref "P7") (pin "12") (pinfunction "12_12") (pintype "passive"))
      (node (ref "U1") (pin "12") (pinfunction "PA4_12") (pintype "bidirectional"))
    )
    (net (code "22") (name "/PA5") (class "Default")
      (node (ref "R42") (pin "2") (pinfunction "2_2") (pintype "passive"))
      (node (ref "U1") (pin "13") (pinfunction "PA5_13") (pintype "bidirectional"))
    )
    (net (code "23") (name "/PA6") (class "Default")
      (node (ref "R43") (pin "2") (pinfunction "2_2") (pintype "passive"))
      (node (ref "U1") (pin "14") (pinfunction "PA6_14") (pintype "bidirectional"))
    )
    (net (code "24") (name "/PA7") (class "Default")
      (node (ref "R44") (pin "2") (pinfunction "2_2") (pintype "passive"))
      (node (ref "U1") (pin "15") (pinfunction "PA7_15") (pintype "bidirectional"))
    )
    (net (code "25") (name "/PA8") (class "Default")
      (node (ref "P8") (pin "7") (pinfunction "7_7") (pintype "passive"))
      (node (ref "P9") (pin "7") (pinfunction "7_7") (pintype "passive"))
      (node (ref "U1") (pin "30") (pinfunction "PA8_30") (pintype "bidirectional"))
    )
    (net (code "26") (name "/PA9") (class "Default")
      (node (ref "R10") (pin "2") (pinfunction "2_2") (pintype "passive"))
      (node (ref "U1") (pin "31") (pinfunction "PA9_31") (pintype "bidirectional"))
    )
    (net (code "27") (name "/PA10") (class "Default")
      (node (ref "R11") (pin "2") (pinfunction "2_2") (pintype "passive"))
      (node (ref "U1") (pin "32") (pinfunction "PA10_32") (pintype "bidirectional"))
    )
    (net (code "28") (name "/PA11") (class "Default")
      (node (ref "NT1") (pin "1") (pinfunction "1_1") (pintype "passive"))
      (node (ref "U1") (pin "33") (pinfunction "PA11_33") (pintype "bidirectional"))
    )
    (net (code "29") (name "/PA12") (class "Default")
      (node (ref "NT4") (pin "1") (pinfunction "1_1") (pintype "passive"))
      (node (ref "U1") (pin "34") (pinfunction "PA12_34") (pintype "bidirectional"))
    )
    (net (code "30") (name "/PA13") (class "Default")
      (node (ref "NT2") (pin "1") (pinfunction "1_1") (pintype "passive"))
      (node (ref "P8") (pin "1") (pinfunction "1_1") (pintype "passive"))
      (node (ref "P9") (pin "1") (pinfunction "1_1") (pintype "passive"))
      (node (ref "U1") (pin "36") (pinfunction "PA13_36") (pintype "bidirectional"))
    )
    (net (code "31") (name "/PA14") (class "Default")
      (node (ref "NT3") (pin "1") (pinfunction "1_1") (pintype "passive"))
      (node (ref "P11") (pin "12") (pinfunction "12_12") (pintype "passive"))
      (node (ref "P12") (pin "12") (pinfunction "12_12") (pintype "passive"))
      (node (ref "U1") (pin "37") (pinfunction "PA14_37") (pintype "bidirectional"))
    )
    (net (code "32") (name "/PA15") (class "Default")
      (node (ref "P11") (pin "11") (pinfunction "11_11") (pintype "passive"))
      (node (ref "P12") (pin "11") (pinfunction "11_11") (pintype "passive"))
      (node (ref "U1") (pin "38") (pinfunction "PA15_38") (pintype "bidirectional"))
    )
    (net (code "33") (name "/PB0") (class "Default")
      (node (ref "R45") (pin "2") (pinfunction "2_2") (pintype "passive"))
      (node (ref "U1") (pin "17") (pinfunction "PB0_17") (pintype "bidirectional"))
    )
    (net (code "34") (name "/PB1") (class "Default")
      (node (ref "R46") (pin "2") (pinfunction "2_2") (pintype "passive"))
      (node (ref "U1") (pin "18") (pinfunction "PB1_18") (pintype "bidirectional"))
    )
    (net (code "35") (name "/PB2") (class "Default")
      (node (ref "R47") (pin "2") (pinfunction "2_2") (pintype "passive"))
      (node (ref "U1") (pin "19") (pinfunction "PB2_19") (pintype "bidirectional"))
    )
    (net (code "36") (name "/PB3") (class "Default")
      (node (ref "P11") (pin "8") (pinfunction "8_8") (pintype "passive"))
      (node (ref "P12") (pin "8") (pinfunction "8_8") (pintype "passive"))
      (node (ref "U1") (pin "41") (pinfunction "PB3_41") (pintype "bidirectional"))
    )
    (net (code "37") (name "/PB4") (class "Default")
      (node (ref "P11") (pin "7") (pinfunction "7_7") (pintype "passive"))
      (node (ref "P12") (pin "7") (pinfunction "7_7") (pintype "passive"))
      (node (ref "U1") (pin "42") (pinfunction "PB4_42") (pintype "bidirectional"))
    )
    (net (code "38") (name "/PB5") (class "Default")
      (node (ref "P11") (pin "6") (pinfunction "6_6") (pintype "passive"))
      (node (ref "P12") (pin "6") (pinfunction "6_6") (pintype "passive"))
      (node (ref "U1") (pin "43") (pinfunction "PB5_43") (pintype "bidirectional"))
    )
    (net (code "39") (name "/PB6") (class "Default")
      (node (ref "P11") (pin "5") (pinfunction "5_5") (pintype "passive"))
      (node (ref "P12") (pin "5") (pinfunction "5_5") (pintype "passive"))
      (node (ref "U1") (pin "44") (pinfunction "PB6_44") (pintype "bidirectional"))
    )
    (net (code "40") (name "/PB7") (class "Default")
      (node (ref "P11") (pin "4") (pinfunction "4_4") (pintype "passive"))
      (node (ref "P12") (pin "4") (pinfunction "4_4") (pintype "passive"))
      (node (ref "U1") (pin "45") (pinfunction "PB7_45") (pintype "bidirectional"))
    )
    (net (code "41") (name "/PB8{slash}BOOT0") (class "Default")
      (node (ref "NT5") (pin "1") (pinfunction "1_1") (pintype "passive"))
      (node (ref "P11") (pin "3") (pinfunction "3_3") (pintype "passive"))
      (node (ref "P12") (pin "3") (pinfunction "3_3") (pintype "passive"))
      (node (ref "U1") (pin "46") (pinfunction "PB8-BOOT0_46") (pintype "bidirectional"))
    )
    (net (code "42") (name "/PB9") (class "Default")
      (node (ref "P11") (pin "2") (pinfunction "2_2") (pintype "passive"))
      (node (ref "P12") (pin "2") (pinfunction "2_2") (pintype "passive"))
      (node (ref "U1") (pin "47") (pinfunction "PB9_47") (pintype "bidirectional"))
    )
    (net (code "43") (name "/PB10") (class "Default")
      (node (ref "R48") (pin "2") (pinfunction "2_2") (pintype "passive"))
      (node (ref "U1") (pin "22") (pinfunction "PB10_22") (pintype "bidirectional"))
    )
    (net (code "44") (name "/PB11") (class "Default")
      (node (ref "P2") (pin "12") (pinfunction "12_12") (pintype "passive"))
      (node (ref "P4") (pin "12") (pinfunction "12_12") (pintype "passive"))
      (node (ref "U1") (pin "24") (pinfunction "PB11_24") (pintype "bidirectional"))
    )
    (net (code "45") (name "/PB12") (class "Default")
      (node (ref "P8") (pin "12") (pinfunction "12_12") (pintype "passive"))
      (node (ref "P9") (pin "12") (pinfunction "12_12") (pintype "passive"))
      (node (ref "U1") (pin "25") (pinfunction "PB12_25") (pintype "bidirectional"))
    )
    (net (code "46") (name "/PB13") (class "Default")
      (node (ref "R41") (pin "2") (pinfunction "2_2") (pintype "passive"))
      (node (ref "U1") (pin "26") (pinfunction "PB13_26") (pintype "bidirectional"))
    )
    (net (code "47") (name "/PB14") (class "Default")
      (node (ref "R39") (pin "2") (pinfunction "2_2") (pintype "passive"))
      (node (ref "U1") (pin "27") (pinfunction "PB14_27") (pintype "bidirectional"))
    )
    (net (code "48") (name "/PB15") (class "Default")
      (node (ref "P8") (pin "9") (pinfunction "9_9") (pintype "passive"))
      (node (ref "P9") (pin "9") (pinfunction "9_9") (pintype "passive"))
      (node (ref "U1") (pin "28") (pinfunction "PB15_28") (pintype "bidirectional"))
    )
    (net (code "49") (name "/PC4") (class "Default")
      (node (ref "P2") (pin "4") (pinfunction "4_4") (pintype "passive"))
      (node (ref "P4") (pin "4") (pinfunction "4_4") (pintype "passive"))
      (node (ref "U1") (pin "16") (pinfunction "PC4_16") (pintype "bidirectional"))
    )
    (net (code "50") (name "/PC6") (class "Default")
      (node (ref "P8") (pin "8") (pinfunction "8_8") (pintype "passive"))
      (node (ref "P9") (pin "8") (pinfunction "8_8") (pintype "passive"))
      (node (ref "U1") (pin "29") (pinfunction "PC6_29") (pintype "bidirectional"))
    )
    (net (code "51") (name "/PC10") (class "Default")
      (node (ref "P11") (pin "10") (pinfunction "10_10") (pintype "passive"))
      (node (ref "P12") (pin "10") (pinfunction "10_10") (pintype "passive"))
      (node (ref "U1") (pin "39") (pinfunction "PC10_39") (pintype "bidirectional"))
    )
    (net (code "52") (name "/PC11") (class "Default")
      (node (ref "P11") (pin "9") (pinfunction "9_9") (pintype "passive"))
      (node (ref "P12") (pin "9") (pinfunction "9_9") (pintype "passive"))
      (node (ref "U1") (pin "40") (pinfunction "PC11_40") (pintype "bidirectional"))
    )
    (net (code "53") (name "/PC13") (class "Default")
      (node (ref "P6") (pin "2") (pinfunction "2_2") (pintype "passive"))
      (node (ref "P7") (pin "2") (pinfunction "2_2") (pintype "passive"))
      (node (ref "R23") (pin "1") (pinfunction "1_1") (pintype "passive"))
      (node (ref "R4") (pin "1") (pinfunction "1_1") (pintype "passive"))
      (node (ref "U1") (pin "2") (pinfunction "PC13_2") (pintype "bidirectional"))
    )
    (net (code "54") (name "/PC14") (class "Default")
      (node (ref "C15") (pin "1") (pinfunction "1_1") (pintype "passive"))
      (node (ref "P6") (pin "3") (pinfunction "3_3") (pintype "passive"))
      (node (ref "P7") (pin "3") (pinfunction "3_3") (pintype "passive"))
      (node (ref "U1") (pin "3") (pinfunction "PC14-OSC32_IN_3") (pintype "bidirectional"))
      (node (ref "X1") (pin "1") (pinfunction "1_1") (pintype "passive"))
    )
    (net (code "55") (name "/PC15") (class "Default")
      (node (ref "C14") (pin "1") (pinfunction "1_1") (pintype "passive"))
      (node (ref "P6") (pin "4") (pinfunction "4_4") (pintype "passive"))
      (node (ref "P7") (pin "4") (pinfunction "4_4") (pintype "passive"))
      (node (ref "U1") (pin "4") (pinfunction "PC15-OSC32_OUT_4") (pintype "bidirectional"))
      (node (ref "X1") (pin "2") (pinfunction "2_2") (pintype "passive"))
    )
    (net (code "56") (name "/PF0") (class "Default")
      (node (ref "C18") (pin "1") (pinfunction "1_1") (pintype "passive"))
      (node (ref "P6") (pin "5") (pinfunction "5_5") (pintype "passive"))
      (node (ref "P7") (pin "5") (pinfunction "5_5") (pintype "passive"))
      (node (ref "U1") (pin "5") (pinfunction "PF0-OSC_IN_5") (pintype "bidirectional"))
      (node (ref "X2") (pin "1") (pinfunction "1_1") (pintype "passive"))
    )
    (net (code "57") (name "/PF1") (class "Default")
      (node (ref "C17") (pin "1") (pinfunction "1_1") (pintype "passive"))
      (node (ref "P6") (pin "6") (pinfunction "6_6") (pintype "passive"))
      (node (ref "P7") (pin "6") (pinfunction "6_6") (pintype "passive"))
      (node (ref "U1") (pin "6") (pinfunction "PF1-OSC_OUT_6") (pintype "bidirectional"))
      (node (ref "X2") (pin "3") (pinfunction "3_3") (pintype "passive"))
    )
    (net (code "58") (name "/PG10{slash}NRST") (class "Default")
      (node (ref "NT6") (pin "2") (pinfunction "2_2") (pintype "passive"))
      (node (ref "P6") (pin "7") (pinfunction "7_7") (pintype "passive"))
      (node (ref "P7") (pin "7") (pinfunction "7_7") (pintype "passive"))
      (node (ref "U1") (pin "7") (pinfunction "PG10-NRST_7") (pintype "bidirectional"))
    )
    (net (code "59") (name "/SWCLK") (class "Default")
      (node (ref "NT3") (pin "2") (pinfunction "2_2") (pintype "passive"))
      (node (ref "P3") (pin "3") (pinfunction "3_3") (pintype "passive"))
    )
    (net (code "60") (name "/SWDIO") (class "Default")
      (node (ref "NT2") (pin "2") (pinfunction "2_2") (pintype "passive"))
      (node (ref "P3") (pin "2") (pinfunction "2_2") (pintype "passive"))
    )
    (net (code "61") (name "/USBFS_D0_N") (class "Default")
      (node (ref "NT1") (pin "2") (pinfunction "2_2") (pintype "passive"))
      (node (ref "R12") (pin "2") (pinfunction "2_2") (pintype "passive"))
      (node (ref "R14") (pin "2") (pinfunction "2_2") (pintype "passive"))
    )
    (net (code "62") (name "/USBFS_D0_P") (class "Default")
      (node (ref "NT4") (pin "2") (pinfunction "2_2") (pintype "passive"))
      (node (ref "R13") (pin "2") (pinfunction "2_2") (pintype "passive"))
      (node (ref "R15") (pin "2") (pinfunction "2_2") (pintype "passive"))
    )
    (net (code "63") (name "/USBFS_D1_N") (class "Default")
      (node (ref "FL1") (pin "4") (pinfunction "4_4") (pintype "passive"))
      (node (ref "R12") (pin "1") (pinfunction "1_1") (pintype "passive"))
    )
    (net (code "64") (name "/USBFS_D1_P") (class "Default")
      (node (ref "FL1") (pin "1") (pinfunction "1_1") (pintype "passive"))
      (node (ref "R13") (pin "1") (pinfunction "1_1") (pintype "passive"))
    )
    (net (code "65") (name "/USBFS_D2_N") (class "Default")
      (node (ref "FL1") (pin "3") (pinfunction "3_3") (pintype "passive"))
      (node (ref "USB1") (pin "A7") (pinfunction "D-_A7") (pintype "passive"))
      (node (ref "USB1") (pin "B7") (pinfunction "D-_B7") (pintype "passive"))
      (node (ref "VD2") (pin "3") (pinfunction "I/O2_3") (pintype "passive"))
      (node (ref "VD2") (pin "4") (pinfunction "I/O2_4") (pintype "passive"))
    )
    (net (code "66") (name "/USBFS_D2_P") (class "Default")
      (node (ref "FL1") (pin "2") (pinfunction "2_2") (pintype "passive"))
      (node (ref "USB1") (pin "A6") (pinfunction "D+_A6") (pintype "passive"))
      (node (ref "USB1") (pin "B6") (pinfunction "D+_B6") (pintype "passive"))
      (node (ref "VD2") (pin "1") (pinfunction "I/O1_1") (pintype "passive"))
      (node (ref "VD2") (pin "6") (pinfunction "I/O1_6") (pintype "passive"))
    )
    (net (code "67") (name "/USBPD_CC1") (class "Default")
      (node (ref "C32") (pin "1") (pinfunction "1_1") (pintype "passive"))
      (node (ref "D6") (pin "2") (pinfunction "2_2") (pintype "passive"))
      (node (ref "P8") (pin "6") (pinfunction "6_6") (pintype "passive"))
      (node (ref "P9") (pin "6") (pinfunction "6_6") (pintype "passive"))
      (node (ref "R10") (pin "1") (pinfunction "1_1") (pintype "passive"))
      (node (ref "USB2") (pin "A5") (pinfunction "CC1_A5") (pintype "passive"))
    )
    (net (code "68") (name "/USBPD_CC2") (class "Default")
      (node (ref "C31") (pin "2") (pinfunction "2_2") (pintype "passive"))
      (node (ref "D5") (pin "2") (pinfunction "2_2") (pintype "passive"))
      (node (ref "P8") (pin "5") (pinfunction "5_5") (pintype "passive"))
      (node (ref "P9") (pin "5") (pinfunction "5_5") (pintype "passive"))
      (node (ref "R11") (pin "1") (pinfunction "1_1") (pintype "passive"))
      (node (ref "USB2") (pin "B5") (pinfunction "CC2_B5") (pintype "passive"))
    )
    (net (code "69") (name "/USBPD_VIN") (class "Default")
      (node (ref "P13") (pin "1") (pinfunction "1_1") (pintype "passive"))
      (node (ref "R35") (pin "1") (pinfunction "1_1") (pintype "passive"))
      (node (ref "U5") (pin "1") (pinfunction "OUT_1") (pintype "output"))
    )
    (net (code "70") (name "3V6") (class "Default")
      (node (ref "C12") (pin "2") (pinfunction "2_2") (pintype "passive"))
      (node (ref "C25") (pin "1") (pinfunction "1_1") (pintype "passive"))
      (node (ref "C26") (pin "1") (pinfunction "1_1") (pintype "passive"))
      (node (ref "C27") (pin "1") (pinfunction "1_1") (pintype "passive"))
      (node (ref "C28") (pin "1") (pinfunction "1_1") (pintype "passive"))
      (node (ref "C41") (pin "2") (pinfunction "2_2") (pintype "passive"))
      (node (ref "L4") (pin "2") (pinfunction "2_2") (pintype "passive"))
      (node (ref "R1") (pin "1") (pinfunction "1_1") (pintype "passive"))
      (node (ref "U2") (pin "1") (pinfunction "VIN_1") (pintype "passive"))
      (node (ref "U2") (pin "3") (pinfunction "EN_3") (pintype "input"))
    )
    (net (code "71") (name "AGND") (class "Default")
      (node (ref "C1") (pin "2") (pinfunction "2_2") (pintype "passive"))
      (node (ref "C2") (pin "1") (pinfunction "1_1") (pintype "passive"))
      (node (ref "C21") (pin "1") (pinfunction "1_1") (pintype "passive"))
      (node (ref "C3") (pin "1") (pinfunction "1_1") (pintype "passive"))
      (node (ref "C35") (pin "2") (pinfunction "2_2") (pintype "passive"))
      (node (ref "C36") (pin "2") (pinfunction "2_2") (pintype "passive"))
      (node (ref "C37") (pin "2") (pinfunction "2_2") (pintype "passive"))
      (node (ref "C4") (pin "1") (pinfunction "1_1") (pintype "passive"))
      (node (ref "C5") (pin "2") (pinfunction "2_2") (pintype "passive"))
      (node (ref "L3") (pin "2") (pinfunction "2_2") (pintype "passive"))
      (node (ref "P10") (pin "1") (pinfunction "1_1") (pintype "passive"))
      (node (ref "P10") (pin "2") (pinfunction "2_2") (pintype "passive"))
      (node (ref "R28") (pin "1") (pinfunction "1_1") (pintype "passive"))
      (node (ref "R32") (pin "1") (pinfunction "1_1") (pintype "passive"))
      (node (ref "U4") (pin "3") (pinfunction "Anode_3") (pintype "passive"))
      (node (ref "U5") (pin "2") (pinfunction "V-_2") (pintype "power_in"))
    )
    (net (code "72") (name "AVDD") (class "Default")
      (node (ref "C3") (pin "2") (pinfunction "2_2") (pintype "passive"))
      (node (ref "C37") (pin "1") (pinfunction "1_1") (pintype "passive"))
      (node (ref "C4") (pin "2") (pinfunction "2_2") (pintype "passive"))
      (node (ref "L2") (pin "2") (pinfunction "2_2") (pintype "passive"))
      (node (ref "P2") (pin "9") (pinfunction "9_9") (pintype "passive"))
      (node (ref "P4") (pin "9") (pinfunction "9_9") (pintype "passive"))
      (node (ref "U1") (pin "21") (pinfunction "VDDA_21") (pintype "power_in"))
      (node (ref "U5") (pin "5") (pinfunction "V+_5") (pintype "power_in"))
    )
    (net (code "73") (name "EX_VBAT") (class "Default")
      (node (ref "P6") (pin "1") (pinfunction "1_1") (pintype "passive"))
      (node (ref "P7") (pin "1") (pinfunction "1_1") (pintype "passive"))
      (node (ref "VD1") (pin "2") (pinfunction "2_2") (pintype "passive"))
    )
    (net (code "74") (name "GND") (class "Default")
      (node (ref "C10") (pin "1") (pinfunction "1_1") (pintype "passive"))
      (node (ref "C11") (pin "1") (pinfunction "1_1") (pintype "passive"))
      (node (ref "C12") (pin "1") (pinfunction "1_1") (pintype "passive"))
      (node (ref "C13") (pin "1") (pinfunction "1_1") (pintype "passive"))
      (node (ref "C14") (pin "2") (pinfunction "2_2") (pintype "passive"))
      (node (ref "C15") (pin "2") (pinfunction "2_2") (pintype "passive"))
      (node (ref "C16") (pin "2") (pinfunction "2_2") (pintype "passive"))
      (node (ref "C17") (pin "2") (pinfunction "2_2") (pintype "passive"))
      (node (ref "C18") (pin "2") (pinfunction "2_2") (pintype "passive"))
      (node (ref "C19") (pin "1") (pinfunction "1_1") (pintype "passive"))
      (node (ref "C20") (pin "1") (pinfunction "1_1") (pintype "passive"))
      (node (ref "C21") (pin "2") (pinfunction "2_2") (pintype "passive"))
      (node (ref "C22") (pin "2") (pinfunction "2_2") (pintype "passive"))
      (node (ref "C23") (pin "2") (pinfunction "2_2") (pintype "passive"))
      (node (ref "C25") (pin "2") (pinfunction "2_2") (pintype "passive"))
      (node (ref "C26") (pin "2") (pinfunction "2_2") (pintype "passive"))
      (node (ref "C27") (pin "2") (pinfunction "2_2") (pintype "passive"))
      (node (ref "C28") (pin "2") (pinfunction "2_2") (pintype "passive"))
      (node (ref "C29") (pin "2") (pinfunction "2_2") (pintype "passive"))
      (node (ref "C31") (pin "1") (pinfunction "1_1") (pintype "passive"))
      (node (ref "C32") (pin "2") (pinfunction "2_2") (pintype "passive"))
      (node (ref "C33") (pin "2") (pinfunction "2_2") (pintype "passive"))
      (node (ref "C38") (pin "2") (pinfunction "2_2") (pintype "passive"))
      (node (ref "C39") (pin "2") (pinfunction "2_2") (pintype "passive"))
      (node (ref "C40") (pin "1") (pinfunction "1_1") (pintype "passive"))
      (node (ref "C41") (pin "1") (pinfunction "1_1") (pintype "passive"))
      (node (ref "C6") (pin "1") (pinfunction "1_1") (pintype "passive"))
      (node (ref "C7") (pin "1") (pinfunction "1_1") (pintype "passive"))
      (node (ref "C8") (pin "1") (pinfunction "1_1") (pintype "passive"))
      (node (ref "C9") (pin "1") (pinfunction "1_1") (pintype "passive"))
      (node (ref "D10") (pin "1") (pinfunction "1_1") (pintype "passive"))
      (node (ref "D11") (pin "1") (pinfunction "1_1") (pintype "passive"))
      (node (ref "D2") (pin "1") (pinfunction "1_1") (pintype "passive"))
      (node (ref "D3") (pin "1") (pinfunction "1_1") (pintype "passive"))
      (node (ref "D4") (pin "1") (pinfunction "1_1") (pintype "passive"))
      (node (ref "D5") (pin "1") (pinfunction "1_1") (pintype "passive"))
      (node (ref "D6") (pin "1") (pinfunction "1_1") (pintype "passive"))
      (node (ref "D7") (pin "1") (pinfunction "1_1") (pintype "passive"))
      (node (ref "L3") (pin "1") (pintype "passive"))
      (node (ref "LED1") (pin "2") (pinfunction "K_2") (pintype "passive"))
      (node (ref "LED2") (pin "2") (pinfunction "K_2") (pintype "passive"))
      (node (ref "P1") (pin "2") (pinfunction "2_2") (pintype "passive"))
      (node (ref "P14") (pin "1") (pinfunction "1_1") (pintype "passive"))
      (node (ref "P14") (pin "2") (pinfunction "2_2") (pintype "passive"))
      (node (ref "P15") (pin "1") (pinfunction "1_1") (pintype "passive"))
      (node (ref "P16") (pin "2") (pinfunction "2_2") (pintype "passive"))
      (node (ref "P17") (pin "1") (pinfunction "1_1") (pintype "passive"))
      (node (ref "P17") (pin "2") (pinfunction "2_2") (pintype "passive"))
      (node (ref "P3") (pin "4") (pinfunction "4_4") (pintype "passive"))
      (node (ref "P5") (pin "2") (pinfunction "2_2") (pintype "passive"))
      (node (ref "R19") (pin "2") (pinfunction "2_2") (pintype "passive"))
      (node (ref "R20") (pin "2") (pinfunction "2_2") (pintype "passive"))
      (node (ref "R28") (pin "2") (pinfunction "2_2") (pintype "passive"))
      (node (ref "R34") (pin "2") (pinfunction "2_2") (pintype "passive"))
      (node (ref "R36") (pin "1") (pinfunction "1_1") (pintype "passive"))
      (node (ref "R49") (pin "1") (pinfunction "1_1") (pintype "passive"))
      (node (ref "R5") (pin "1") (pinfunction "1_1") (pintype "passive"))
      (node (ref "R50") (pin "2") (pinfunction "2_2") (pintype "passive"))
      (node (ref "R7") (pin "2") (pinfunction "2_2") (pintype "passive"))
      (node (ref "R9") (pin "2") (pinfunction "2_2") (pintype "passive"))
      (node (ref "SW2") (pin "3") (pinfunction "3_3") (pintype "passive"))
      (node (ref "SW2") (pin "4") (pinfunction "4_4") (pintype "passive"))
      (node (ref "U1") (pin "49") (pinfunction "EPAD_49") (pintype "passive"))
      (node (ref "U2") (pin "2") (pinfunction "GND_2") (pintype "passive"))
      (node (ref "U3") (pin "1") (pinfunction "GND_1") (pintype "passive"))
      (node (ref "USB1") (pin "A1") (pinfunction "GND_A1") (pintype "passive"))
      (node (ref "USB1") (pin "A12") (pinfunction "GND_A12") (pintype "passive"))
      (node (ref "USB1") (pin "B1") (pinfunction "GND_B1") (pintype "passive"))
      (node (ref "USB1") (pin "B12") (pinfunction "GND_B12") (pintype "passive"))
      (node (ref "USB2") (pin "A1") (pinfunction "GND_A1") (pintype "passive"))
      (node (ref "USB2") (pin "A12") (pinfunction "GND_A12") (pintype "passive"))
      (node (ref "USB2") (pin "B1") (pinfunction "GND_B1") (pintype "passive"))
      (node (ref "USB2") (pin "B12") (pinfunction "GND_B12") (pintype "passive"))
      (node (ref "VD2") (pin "2") (pinfunction "GND_2") (pintype "passive"))
      (node (ref "X2") (pin "2") (pinfunction "GND_2") (pintype "passive"))
      (node (ref "X2") (pin "4") (pinfunction "GND_4") (pintype "passive"))
    )
    (net (code "75") (name "Net-(C19-Pad2)") (class "Default")
      (node (ref "C19") (pin "2") (pinfunction "2_2") (pintype "passive"))
      (node (ref "R23") (pin "2") (pinfunction "2_2") (pintype "passive"))
      (node (ref "R24") (pin "2") (pinfunction "2_2") (pintype "passive"))
      (node (ref "R25") (pin "2") (pinfunction "2_2") (pintype "passive"))
      (node (ref "R6") (pin "1") (pinfunction "1_1") (pintype "passive"))
    )
    (net (code "76") (name "Net-(C30-Pad1)") (class "Default")
      (node (ref "C30") (pin "1") (pinfunction "1_1") (pintype "passive"))
      (node (ref "R1") (pin "2") (pinfunction "2_2") (pintype "passive"))
      (node (ref "R16") (pin "1") (pinfunction "1_1") (pintype "passive"))
    )
    (net (code "77") (name "Net-(D2-Pad2)") (class "Default")
      (node (ref "D2") (pin "2") (pinfunction "2_2") (pintype "passive"))
      (node (ref "R6") (pin "2") (pinfunction "2_2") (pintype "passive"))
      (node (ref "R7") (pin "1") (pinfunction "1_1") (pintype "passive"))
      (node (ref "SW1") (pin "1") (pinfunction "1_1") (pintype "passive"))
      (node (ref "SW1") (pin "2") (pinfunction "2_2") (pintype "passive"))
    )
    (net (code "78") (name "Net-(D8-C)") (class "Default")
      (node (ref "C22") (pin "1") (pinfunction "1_1") (pintype "passive"))
      (node (ref "C23") (pin "1") (pinfunction "1_1") (pintype "passive"))
      (node (ref "D8") (pin "2") (pinfunction "C_2") (pintype "passive"))
      (node (ref "D9") (pin "2") (pinfunction "C_2") (pintype "passive"))
      (node (ref "R3") (pin "1") (pinfunction "1_1") (pintype "passive"))
      (node (ref "U3") (pin "3") (pinfunction "VIN_3") (pintype "passive"))
    )
    (net (code "79") (name "Net-(LED1-A)") (class "Default")
      (node (ref "LED1") (pin "1") (pinfunction "A_1") (pintype "passive"))
      (node (ref "R2") (pin "2") (pinfunction "2_2") (pintype "passive"))
    )
    (net (code "80") (name "Net-(LED2-A)") (class "Default")
      (node (ref "LED2") (pin "1") (pinfunction "A_1") (pintype "passive"))
      (node (ref "R4") (pin "2") (pinfunction "2_2") (pintype "passive"))
    )
    (net (code "81") (name "Net-(Q1-B)") (class "Default")
      (node (ref "C34") (pin "2") (pinfunction "2_2") (pintype "passive"))
      (node (ref "Q1") (pin "1") (pinfunction "B_1") (pintype "passive"))
      (node (ref "R29") (pin "1") (pinfunction "1_1") (pintype "passive"))
      (node (ref "U4") (pin "1") (pinfunction "Cathode_1") (pintype "passive"))
    )
    (net (code "82") (name "Net-(U2-NC)") (class "Default")
      (node (ref "C33") (pin "1") (pinfunction "1_1") (pintype "passive"))
      (node (ref "U2") (pin "4") (pinfunction "NC_4") (pintype "passive"))
    )
    (net (code "83") (name "Net-(U3-BOOT)") (class "Default")
      (node (ref "C24") (pin "1") (pinfunction "1_1") (pintype "passive"))
      (node (ref "U3") (pin "6") (pinfunction "BOOT_6") (pintype "passive"))
    )
    (net (code "84") (name "Net-(U3-EN)") (class "Default")
      (node (ref "R20") (pin "1") (pinfunction "1_1") (pintype "passive"))
      (node (ref "R3") (pin "2") (pinfunction "2_2") (pintype "passive"))
      (node (ref "U3") (pin "5") (pinfunction "EN_5") (pintype "passive"))
    )
    (net (code "85") (name "Net-(U3-FB)") (class "Default")
      (node (ref "C30") (pin "2") (pinfunction "2_2") (pintype "passive"))
      (node (ref "R16") (pin "2") (pinfunction "2_2") (pintype "passive"))
      (node (ref "R19") (pin "1") (pinfunction "1_1") (pintype "passive"))
      (node (ref "U3") (pin "4") (pinfunction "FB_4") (pintype "passive"))
    )
    (net (code "86") (name "Net-(U3-SW)") (class "Default")
      (node (ref "C24") (pin "2") (pinfunction "2_2") (pintype "passive"))
      (node (ref "L4") (pin "1") (pintype "passive"))
      (node (ref "U3") (pin "2") (pinfunction "SW_2") (pintype "passive"))
    )
    (net (code "87") (name "Net-(U4-Ref)") (class "Default")
      (node (ref "C34") (pin "1") (pinfunction "1_1") (pintype "passive"))
      (node (ref "R30") (pin "1") (pinfunction "1_1") (pintype "passive"))
      (node (ref "R31") (pin "1") (pinfunction "1_1") (pintype "passive"))
      (node (ref "R32") (pin "2") (pinfunction "2_2") (pintype "passive"))
      (node (ref "U4") (pin "2") (pinfunction "Ref_2") (pintype "passive"))
    )
    (net (code "88") (name "Net-(U5-IN+)") (class "Default")
      (node (ref "C38") (pin "1") (pinfunction "1_1") (pintype "passive"))
      (node (ref "R33") (pin "1") (pinfunction "1_1") (pintype "passive"))
      (node (ref "R34") (pin "1") (pinfunction "1_1") (pintype "passive"))
      (node (ref "U5") (pin "3") (pinfunction "IN+_3") (pintype "input"))
    )
    (net (code "89") (name "Net-(U5-IN-)") (class "Default")
      (node (ref "R35") (pin "2") (pinfunction "2_2") (pintype "passive"))
      (node (ref "U5") (pin "4") (pinfunction "IN-_4") (pintype "input"))
    )
    (net (code "90") (name "Net-(USB1-CC1)") (class "Default")
      (node (ref "R49") (pin "2") (pinfunction "2_2") (pintype "passive"))
      (node (ref "USB1") (pin "A5") (pinfunction "CC1_A5") (pintype "passive"))
    )
    (net (code "91") (name "Net-(USB1-CC2)") (class "Default")
      (node (ref "R50") (pin "1") (pinfunction "1_1") (pintype "passive"))
      (node (ref "USB1") (pin "B5") (pinfunction "CC2_B5") (pintype "passive"))
    )
    (net (code "92") (name "Net-(USB1-SH1)") (class "Default")
      (node (ref "C11") (pin "2") (pinfunction "2_2") (pintype "passive"))
      (node (ref "R5") (pin "2") (pinfunction "2_2") (pintype "passive"))
      (node (ref "USB1") (pin "1") (pinfunction "SH1_1") (pintype "passive"))
      (node (ref "USB1") (pin "2") (pinfunction "SH2_2") (pintype "passive"))
      (node (ref "USB1") (pin "3") (pinfunction "SH3_3") (pintype "passive"))
      (node (ref "USB1") (pin "4") (pinfunction "SH4_4") (pintype "passive"))
    )
    (net (code "93") (name "Net-(USB2-SH1)") (class "Default")
      (node (ref "C40") (pin "2") (pinfunction "2_2") (pintype "passive"))
      (node (ref "R36") (pin "2") (pinfunction "2_2") (pintype "passive"))
      (node (ref "USB2") (pin "1") (pinfunction "SH1_1") (pintype "passive"))
      (node (ref "USB2") (pin "2") (pinfunction "SH2_2") (pintype "passive"))
      (node (ref "USB2") (pin "3") (pinfunction "SH3_3") (pintype "passive"))
      (node (ref "USB2") (pin "4") (pinfunction "SH4_4") (pintype "passive"))
    )
    (net (code "94") (name "USBFS_VBUS") (class "Default")
      (node (ref "C16") (pin "1") (pinfunction "1_1") (pintype "passive"))
      (node (ref "D7") (pin "2") (pinfunction "2_2") (pintype "passive"))
      (node (ref "D9") (pin "1") (pinfunction "A_1") (pintype "passive"))
      (node (ref "P15") (pin "2") (pinfunction "2_2") (pintype "passive"))
      (node (ref "P5") (pin "1") (pinfunction "1_1") (pintype "passive"))
      (node (ref "Q1") (pin "3") (pinfunction "C_3") (pintype "passive"))
      (node (ref "R29") (pin "2") (pinfunction "2_2") (pintype "passive"))
      (node (ref "USB1") (pin "A4") (pinfunction "VBUS_A4") (pintype "passive"))
      (node (ref "USB1") (pin "A9") (pinfunction "VBUS_A9") (pintype "passive"))
      (node (ref "USB1") (pin "B4") (pinfunction "VBUS_B4") (pintype "passive"))
      (node (ref "USB1") (pin "B9") (pinfunction "VBUS_B9") (pintype "passive"))
    )
    (net (code "95") (name "USBPD_VBUS") (class "Default")
      (node (ref "C39") (pin "1") (pinfunction "1_1") (pintype "passive"))
      (node (ref "D10") (pin "2") (pinfunction "2_2") (pintype "passive"))
      (node (ref "D8") (pin "1") (pinfunction "A_1") (pintype "passive"))
      (node (ref "P1") (pin "1") (pinfunction "1_1") (pintype "passive"))
      (node (ref "P16") (pin "1") (pinfunction "1_1") (pintype "passive"))
      (node (ref "R33") (pin "2") (pinfunction "2_2") (pintype "passive"))
      (node (ref "USB2") (pin "A4") (pinfunction "VBUS_A4") (pintype "passive"))
      (node (ref "USB2") (pin "A9") (pinfunction "VBUS_A9") (pintype "passive"))
      (node (ref "USB2") (pin "B4") (pinfunction "VBUS_B4") (pintype "passive"))
      (node (ref "USB2") (pin "B9") (pinfunction "VBUS_B9") (pintype "passive"))
    )
    (net (code "96") (name "VBAT") (class "Default")
      (node (ref "C6") (pin "2") (pinfunction "2_2") (pintype "passive"))
      (node (ref "R27") (pin "2") (pinfunction "2_2") (pintype "passive"))
      (node (ref "SW1") (pin "3") (pinfunction "3_3") (pintype "passive"))
      (node (ref "SW1") (pin "4") (pinfunction "4_4") (pintype "passive"))
      (node (ref "U1") (pin "1") (pinfunction "VBAT_1") (pintype "power_in"))
      (node (ref "VD1") (pin "3") (pinfunction "3_3") (pintype "passive"))
    )
    (net (code "97") (name "VDD") (class "Default")
      (node (ref "C10") (pin "2") (pinfunction "2_2") (pintype "passive"))
      (node (ref "C13") (pin "2") (pinfunction "2_2") (pintype "passive"))
      (node (ref "C29") (pin "1") (pinfunction "1_1") (pintype "passive"))
      (node (ref "C7") (pin "2") (pinfunction "2_2") (pintype "passive"))
      (node (ref "C8") (pin "2") (pinfunction "2_2") (pintype "passive"))
      (node (ref "C9") (pin "2") (pinfunction "2_2") (pintype "passive"))
      (node (ref "D11") (pin "2") (pinfunction "2_2") (pintype "passive"))
      (node (ref "L2") (pin "1") (pintype "passive"))
      (node (ref "P11") (pin "1") (pinfunction "1_1") (pintype "passive"))
      (node (ref "P12") (pin "1") (pinfunction "1_1") (pintype "passive"))
      (node (ref "P2") (pin "11") (pinfunction "11_11") (pintype "passive"))
      (node (ref "P3") (pin "1") (pinfunction "1_1") (pintype "passive"))
      (node (ref "P4") (pin "11") (pinfunction "11_11") (pintype "passive"))
      (node (ref "P8") (pin "2") (pinfunction "2_2") (pintype "passive"))
      (node (ref "P9") (pin "2") (pinfunction "2_2") (pintype "passive"))
      (node (ref "R2") (pin "1") (pinfunction "1_1") (pintype "passive"))
      (node (ref "R26") (pin "1") (pinfunction "1_1") (pintype "passive"))
      (node (ref "R27") (pin "1") (pinfunction "1_1") (pintype "passive"))
      (node (ref "R8") (pin "1") (pinfunction "1_1") (pintype "passive"))
      (node (ref "SW3") (pin "3") (pinfunction "3_3") (pintype "passive"))
      (node (ref "SW3") (pin "4") (pinfunction "4_4") (pintype "passive"))
      (node (ref "U1") (pin "23") (pinfunction "VDD_23") (pintype "power_in"))
      (node (ref "U1") (pin "35") (pinfunction "VDD_35") (pintype "power_in"))
      (node (ref "U1") (pin "48") (pinfunction "VDD_48") (pintype "power_in"))
      (node (ref "U2") (pin "5") (pinfunction "VOUT_5") (pintype "passive"))
      (node (ref "VD1") (pin "1") (pinfunction "1_1") (pintype "passive"))
    )
    (net (code "98") (name "VREF") (class "Default")
      (node (ref "C2") (pin "2") (pinfunction "2_2") (pintype "passive"))
      (node (ref "C35") (pin "1") (pinfunction "1_1") (pintype "passive"))
      (node (ref "C36") (pin "1") (pinfunction "1_1") (pintype "passive"))
      (node (ref "L1") (pin "1") (pintype "passive"))
      (node (ref "P2") (pin "8") (pinfunction "8_8") (pintype "passive"))
      (node (ref "P4") (pin "8") (pinfunction "8_8") (pintype "passive"))
      (node (ref "Q1") (pin "2") (pinfunction "E_2") (pintype "passive"))
      (node (ref "R26") (pin "2") (pinfunction "2_2") (pintype "passive"))
      (node (ref "R30") (pin "2") (pinfunction "2_2") (pintype "passive"))
      (node (ref "R31") (pin "2") (pinfunction "2_2") (pintype "passive"))
    )
    (net (code "99") (name "VREFP") (class "Default")
      (node (ref "C1") (pin "1") (pinfunction "1_1") (pintype "passive"))
      (node (ref "C5") (pin "1") (pinfunction "1_1") (pintype "passive"))
      (node (ref "L1") (pin "2") (pinfunction "2_2") (pintype "passive"))
      (node (ref "U1") (pin "20") (pinfunction "VREF+_20") (pintype "power_in"))
    )
    (net (code "100") (name "unconnected-(H1-Pad1)") (class "Default")
      (node (ref "H1") (pin "1") (pinfunction "1_1") (pintype "passive"))
    )
    (net (code "101") (name "unconnected-(H2-Pad1)") (class "Default")
      (node (ref "H2") (pin "1") (pinfunction "1_1") (pintype "passive"))
    )
    (net (code "102") (name "unconnected-(H3-Pad1)") (class "Default")
      (node (ref "H3") (pin "1") (pinfunction "1_1") (pintype "passive"))
    )
    (net (code "103") (name "unconnected-(H4-Pad1)") (class "Default")
      (node (ref "H4") (pin "1") (pinfunction "1_1") (pintype "passive"))
    )
    (net (code "104") (name "unconnected-(USB1-SBU1-PadA8)") (class "Default")
      (node (ref "USB1") (pin "A8") (pinfunction "SBU1_A8") (pintype "passive+no_connect"))
    )
    (net (code "105") (name "unconnected-(USB1-SBU2-PadB8)") (class "Default")
      (node (ref "USB1") (pin "B8") (pinfunction "SBU2_B8") (pintype "passive+no_connect"))
    )
    (net (code "106") (name "unconnected-(USB2-D+-PadA6)") (class "Default")
      (node (ref "USB2") (pin "A6") (pinfunction "D+_A6") (pintype "passive+no_connect"))
    )
    (net (code "107") (name "unconnected-(USB2-D+-PadB6)") (class "Default")
      (node (ref "USB2") (pin "B6") (pinfunction "D+_B6") (pintype "passive+no_connect"))
    )
    (net (code "108") (name "unconnected-(USB2-D--PadA7)") (class "Default")
      (node (ref "USB2") (pin "A7") (pinfunction "D-_A7") (pintype "passive+no_connect"))
    )
    (net (code "109") (name "unconnected-(USB2-D--PadB7)") (class "Default")
      (node (ref "USB2") (pin "B7") (pinfunction "D-_B7") (pintype "passive+no_connect"))
    )
    (net (code "110") (name "unconnected-(USB2-SBU1-PadA8)") (class "Default")
      (node (ref "USB2") (pin "A8") (pinfunction "SBU1_A8") (pintype "passive+no_connect"))
    )
    (net (code "111") (name "unconnected-(USB2-SBU2-PadB8)") (class "Default")
      (node (ref "USB2") (pin "B8") (pinfunction "SBU2_B8") (pintype "passive+no_connect"))
    )
    (net (code "112") (name "unconnected-(VD2-VBUS-Pad5)") (class "Default")
      (node (ref "VD2") (pin "5") (pinfunction "VBUS_5") (pintype "passive+no_connect"))
    )
  )
)
